# pi-shield.net
KiCad netlist of a schematic drawn in EAGLE
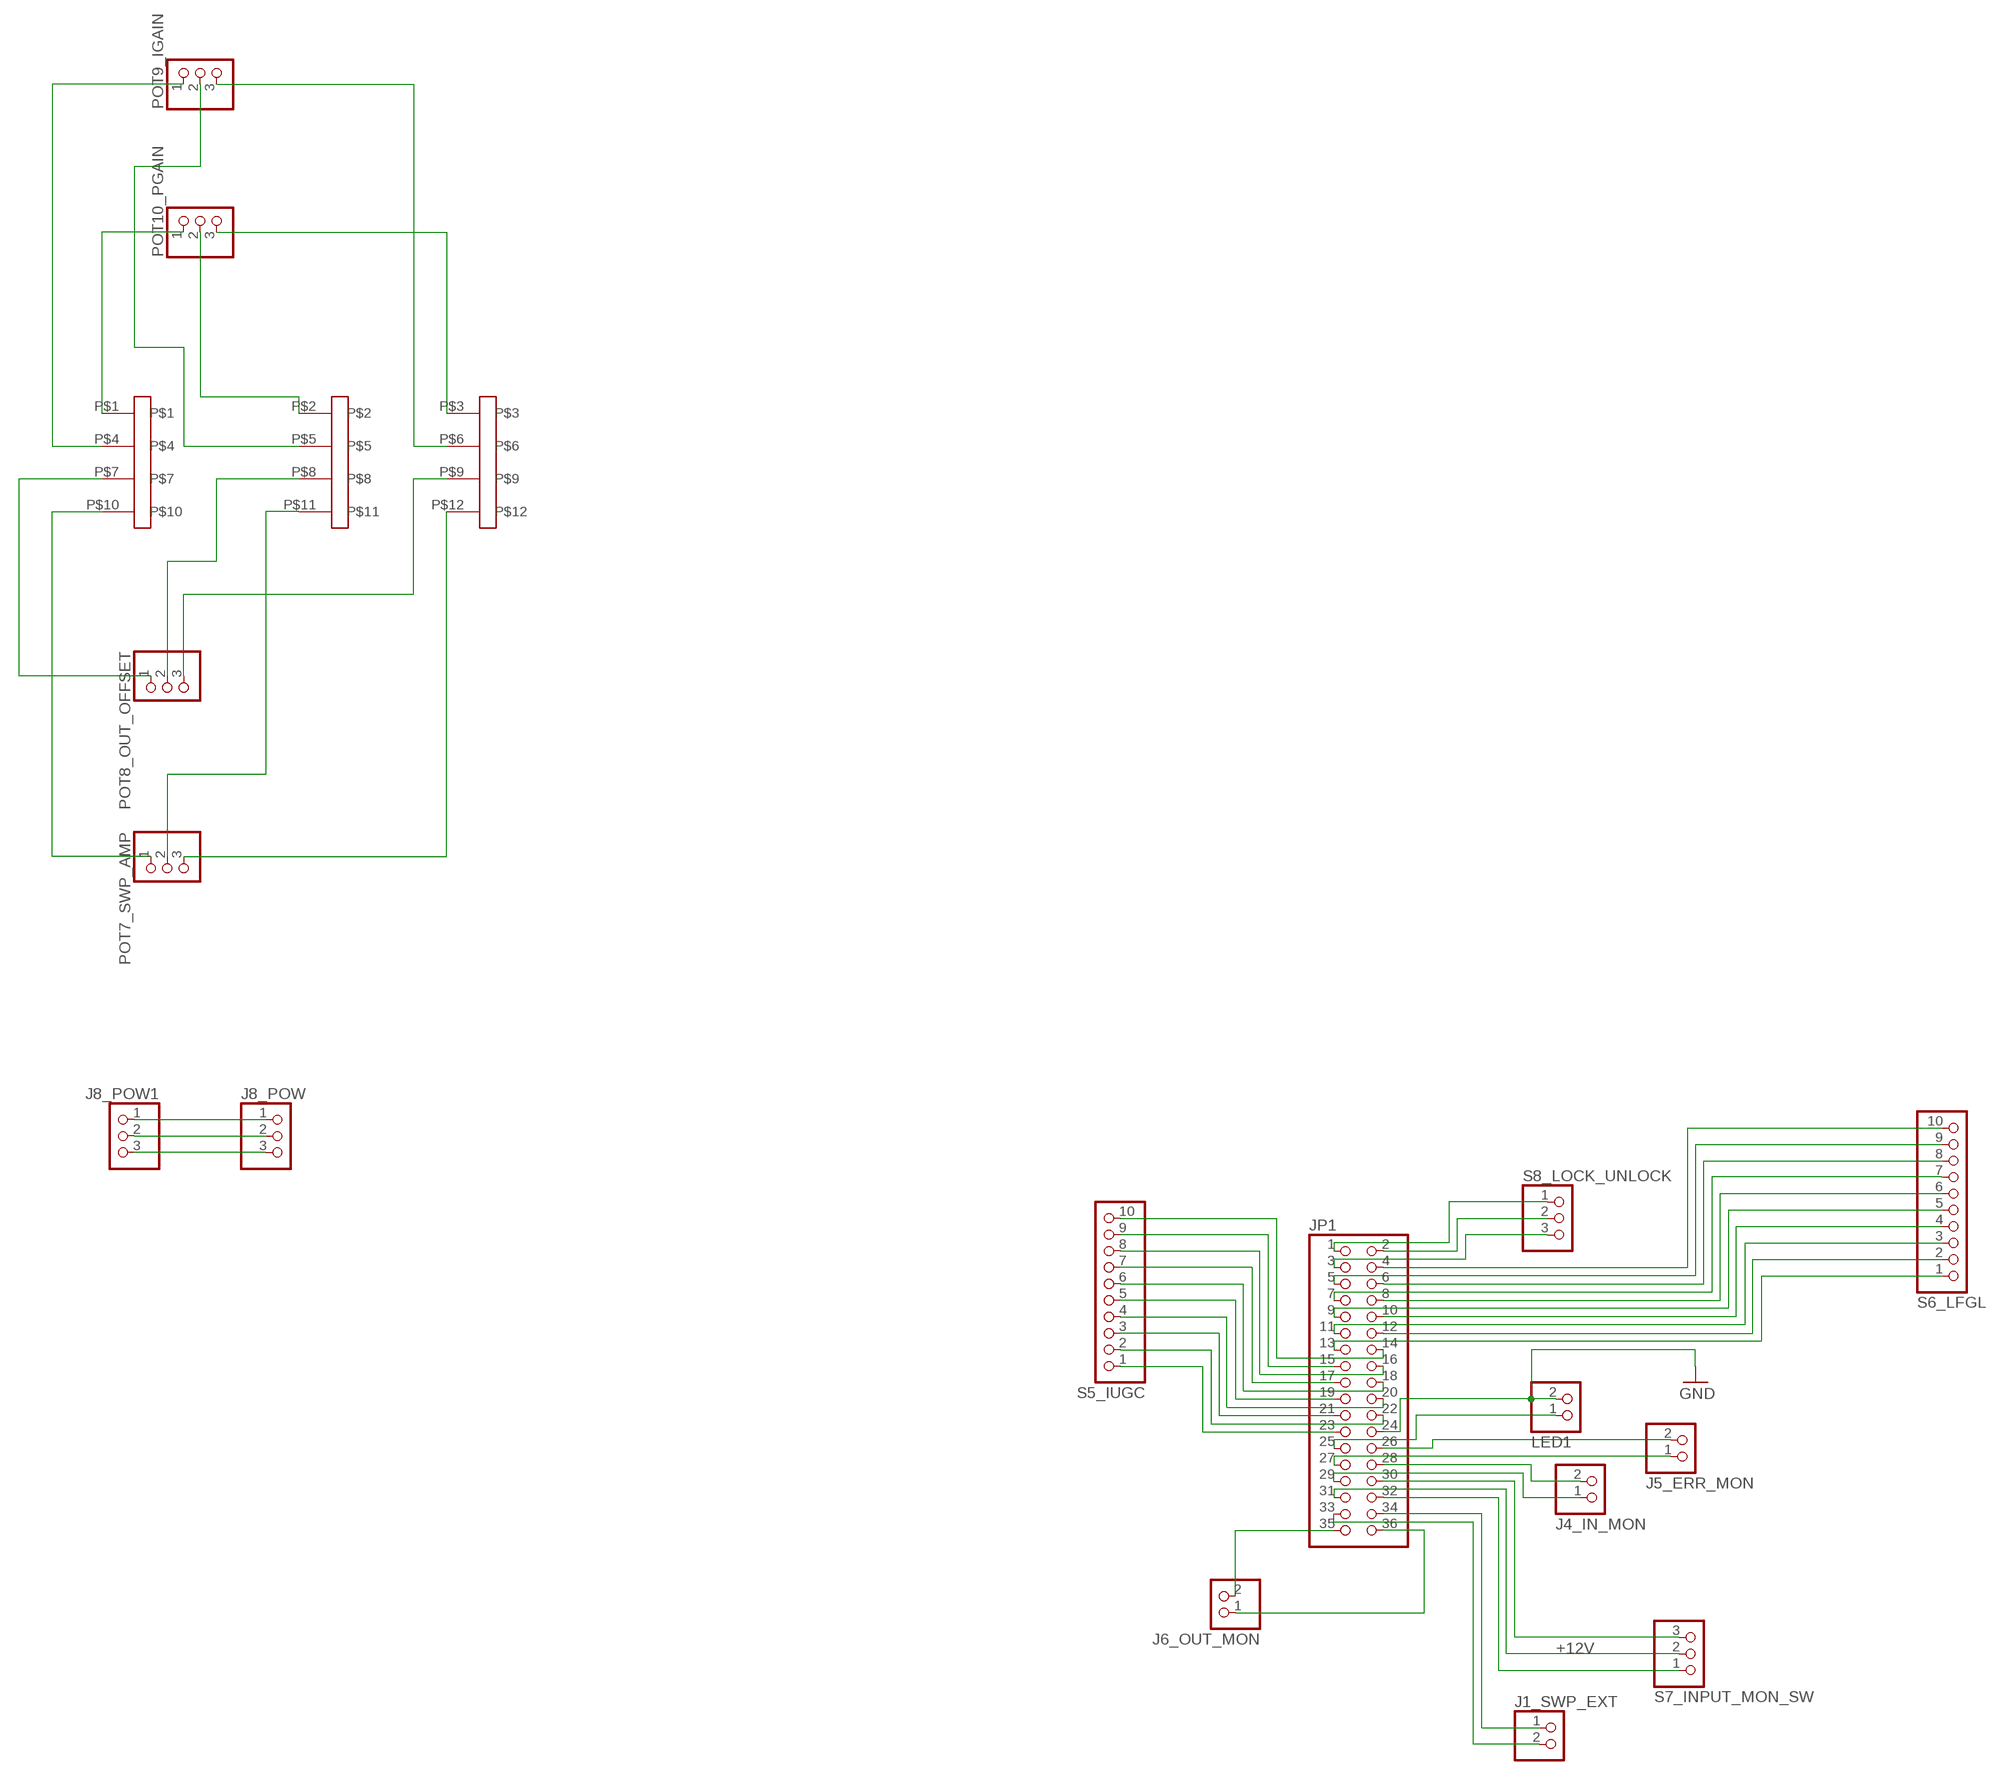
[diagram p0: schematic, sheet 1]

(export (version "E")
  (design (tool "Eeschema 10.0.6"))
  (components
    (comp (ref "J1")
      (value "PINHD-3X4")
      (footprint "eagle-import:3X04")
      (fields (field (name "PARTNO") "S7071-ND (2x)"))
      (libsource (lib "eagle-import") (part "PINHD-3X4"))
    )
    (comp (ref "J1_SWP_EXT")
      (value "PINHD-1X2")
      (footprint "eagle-import:1X02")
      (fields (field (name "PARTNO") "S7000-ND"))
      (libsource (lib "eagle-import") (part "PINHD-1X2"))
    )
    (comp (ref "J4_IN_MON")
      (value "PINHD-1X2")
      (footprint "eagle-import:1X02")
      (fields (field (name "PARTNO") "S7000-ND"))
      (libsource (lib "eagle-import") (part "PINHD-1X2"))
    )
    (comp (ref "J5_ERR_MON")
      (value "PINHD-1X2")
      (footprint "eagle-import:1X02")
      (fields (field (name "PARTNO") "S7000-ND"))
      (libsource (lib "eagle-import") (part "PINHD-1X2"))
    )
    (comp (ref "J6_OUT_MON")
      (value "PINHD-1X2")
      (footprint "eagle-import:1X02")
      (fields (field (name "PARTNO") "S7000-ND"))
      (libsource (lib "eagle-import") (part "PINHD-1X2"))
    )
    (comp (ref "J8_POW")
      (value "PINHD-1X3")
      (footprint "eagle-import:1X03")
      (fields (field (name "PARTNO") "S7036-ND"))
      (libsource (lib "eagle-import") (part "PINHD-1X3"))
    )
    (comp (ref "J8_POW1")
      (value "PINHD-1X3")
      (footprint "eagle-import:1X03")
      (fields (field (name "PARTNO") "A19470-ND"))
      (libsource (lib "eagle-import") (part "PINHD-1X3"))
    )
    (comp (ref "JP1")
      (value "PINHD-2X18/90")
      (footprint "eagle-import:2X18_90")
      (fields (field (name "PARTNO") "S2111EC-18-ND"))
      (libsource (lib "eagle-import") (part "PINHD-2X18/90"))
    )
    (comp (ref "LED1")
      (value "PINHD-1X2")
      (footprint "eagle-import:1X02")
      (fields (field (name "PARTNO") "S7000-ND"))
      (libsource (lib "eagle-import") (part "PINHD-1X2"))
    )
    (comp (ref "POT7_SWP_AMP")
      (value "PINHD-1X3")
      (footprint "eagle-import:1X03")
      (fields (field (name "PARTNO") "S7036-ND"))
      (libsource (lib "eagle-import") (part "PINHD-1X3"))
    )
    (comp (ref "POT8_OUT_OFFSET")
      (value "PINHD-1X3")
      (footprint "eagle-import:1X03")
      (fields (field (name "PARTNO") "S7036-ND"))
      (libsource (lib "eagle-import") (part "PINHD-1X3"))
    )
    (comp (ref "POT9_IGAIN")
      (value "PINHD-1X3")
      (footprint "eagle-import:1X03")
      (fields (field (name "PARTNO") "S7036-ND"))
      (libsource (lib "eagle-import") (part "PINHD-1X3"))
    )
    (comp (ref "POT10_PGAIN")
      (value "PINHD-1X3")
      (footprint "eagle-import:1X03")
      (fields (field (name "PARTNO") "S7036-ND"))
      (libsource (lib "eagle-import") (part "PINHD-1X3"))
    )
    (comp (ref "S5_IUGC")
      (value "PINHD-1X10")
      (footprint "eagle-import:1X10")
      (fields (field (name "PARTNO") "S7008-ND"))
      (libsource (lib "eagle-import") (part "PINHD-1X10"))
    )
    (comp (ref "S6_LFGL")
      (value "PINHD-1X10")
      (footprint "eagle-import:1X10")
      (fields (field (name "PARTNO") "S7008-ND"))
      (libsource (lib "eagle-import") (part "PINHD-1X10"))
    )
    (comp (ref "S7_INPUT_MON_SW")
      (value "PINHD-1X3")
      (footprint "eagle-import:1X03")
      (fields (field (name "PARTNO") "S7036-ND"))
      (libsource (lib "eagle-import") (part "PINHD-1X3"))
    )
    (comp (ref "S8_LOCK_UNLOCK")
      (value "PINHD-1X3")
      (footprint "eagle-import:1X03")
      (fields (field (name "PARTNO") "S7036-ND"))
      (libsource (lib "eagle-import") (part "PINHD-1X3"))
    )
  )
  (nets
    (net (code "1") (name "/+12V") (class "Default")
      (node (ref "JP1") (pin "31") (pinfunction "31_31") (pintype "passive"))
      (node (ref "S7_INPUT_MON_SW") (pin "2") (pinfunction "2_2") (pintype "passive"))
    )
    (net (code "2") (name "GND") (class "Default")
      (node (ref "JP1") (pin "24") (pinfunction "24_24") (pintype "passive"))
      (node (ref "LED1") (pin "2") (pinfunction "2_2") (pintype "passive"))
    )
    (net (code "3") (name "Net-(J1-PadP$1)") (class "Default")
      (node (ref "J1") (pin "P$1") (pinfunction "P$1_P$1") (pintype "bidirectional"))
      (node (ref "POT10_PGAIN") (pin "1") (pinfunction "1_1") (pintype "passive"))
    )
    (net (code "4") (name "Net-(J1-PadP$2)") (class "Default")
      (node (ref "J1") (pin "P$2") (pinfunction "P$2_P$2") (pintype "bidirectional"))
      (node (ref "POT10_PGAIN") (pin "2") (pinfunction "2_2") (pintype "passive"))
    )
    (net (code "5") (name "Net-(J1-PadP$3)") (class "Default")
      (node (ref "J1") (pin "P$3") (pinfunction "P$3_P$3") (pintype "bidirectional"))
      (node (ref "POT10_PGAIN") (pin "3") (pinfunction "3_3") (pintype "passive"))
    )
    (net (code "6") (name "Net-(J1-PadP$4)") (class "Default")
      (node (ref "J1") (pin "P$4") (pinfunction "P$4_P$4") (pintype "bidirectional"))
      (node (ref "POT9_IGAIN") (pin "1") (pinfunction "1_1") (pintype "passive"))
    )
    (net (code "7") (name "Net-(J1-PadP$5)") (class "Default")
      (node (ref "J1") (pin "P$5") (pinfunction "P$5_P$5") (pintype "bidirectional"))
      (node (ref "POT9_IGAIN") (pin "2") (pinfunction "2_2") (pintype "passive"))
    )
    (net (code "8") (name "Net-(J1-PadP$6)") (class "Default")
      (node (ref "J1") (pin "P$6") (pinfunction "P$6_P$6") (pintype "bidirectional"))
      (node (ref "POT9_IGAIN") (pin "3") (pinfunction "3_3") (pintype "passive"))
    )
    (net (code "9") (name "Net-(J1-PadP$7)") (class "Default")
      (node (ref "J1") (pin "P$7") (pinfunction "P$7_P$7") (pintype "bidirectional"))
      (node (ref "POT8_OUT_OFFSET") (pin "1") (pinfunction "1_1") (pintype "passive"))
    )
    (net (code "10") (name "Net-(J1-PadP$8)") (class "Default")
      (node (ref "J1") (pin "P$8") (pinfunction "P$8_P$8") (pintype "bidirectional"))
      (node (ref "POT8_OUT_OFFSET") (pin "2") (pinfunction "2_2") (pintype "passive"))
    )
    (net (code "11") (name "Net-(J1-PadP$9)") (class "Default")
      (node (ref "J1") (pin "P$9") (pinfunction "P$9_P$9") (pintype "bidirectional"))
      (node (ref "POT8_OUT_OFFSET") (pin "3") (pinfunction "3_3") (pintype "passive"))
    )
    (net (code "12") (name "Net-(J1-PadP$10)") (class "Default")
      (node (ref "J1") (pin "P$10") (pinfunction "P$10_P$10") (pintype "bidirectional"))
      (node (ref "POT7_SWP_AMP") (pin "1") (pinfunction "1_1") (pintype "passive"))
    )
    (net (code "13") (name "Net-(J1-PadP$11)") (class "Default")
      (node (ref "J1") (pin "P$11") (pinfunction "P$11_P$11") (pintype "bidirectional"))
      (node (ref "POT7_SWP_AMP") (pin "2") (pinfunction "2_2") (pintype "passive"))
    )
    (net (code "14") (name "Net-(J1-PadP$12)") (class "Default")
      (node (ref "J1") (pin "P$12") (pinfunction "P$12_P$12") (pintype "bidirectional"))
      (node (ref "POT7_SWP_AMP") (pin "3") (pinfunction "3_3") (pintype "passive"))
    )
    (net (code "15") (name "Net-(J1_SWP_EXT-Pad1)") (class "Default")
      (node (ref "J1_SWP_EXT") (pin "1") (pinfunction "1_1") (pintype "passive"))
      (node (ref "JP1") (pin "34") (pinfunction "34_34") (pintype "passive"))
    )
    (net (code "16") (name "Net-(J1_SWP_EXT-Pad2)") (class "Default")
      (node (ref "J1_SWP_EXT") (pin "2") (pinfunction "2_2") (pintype "passive"))
      (node (ref "JP1") (pin "33") (pinfunction "33_33") (pintype "passive"))
    )
    (net (code "17") (name "Net-(J4_IN_MON-Pad1)") (class "Default")
      (node (ref "J4_IN_MON") (pin "1") (pinfunction "1_1") (pintype "passive"))
      (node (ref "JP1") (pin "29") (pinfunction "29_29") (pintype "passive"))
    )
    (net (code "18") (name "Net-(J4_IN_MON-Pad2)") (class "Default")
      (node (ref "J4_IN_MON") (pin "2") (pinfunction "2_2") (pintype "passive"))
      (node (ref "JP1") (pin "28") (pinfunction "28_28") (pintype "passive"))
    )
    (net (code "19") (name "Net-(J5_ERR_MON-Pad1)") (class "Default")
      (node (ref "J5_ERR_MON") (pin "1") (pinfunction "1_1") (pintype "passive"))
      (node (ref "JP1") (pin "27") (pinfunction "27_27") (pintype "passive"))
    )
    (net (code "20") (name "Net-(J5_ERR_MON-Pad2)") (class "Default")
      (node (ref "J5_ERR_MON") (pin "2") (pinfunction "2_2") (pintype "passive"))
      (node (ref "JP1") (pin "26") (pinfunction "26_26") (pintype "passive"))
    )
    (net (code "21") (name "Net-(J6_OUT_MON-Pad1)") (class "Default")
      (node (ref "J6_OUT_MON") (pin "1") (pinfunction "1_1") (pintype "passive"))
      (node (ref "JP1") (pin "36") (pinfunction "36_36") (pintype "passive"))
    )
    (net (code "22") (name "Net-(J6_OUT_MON-Pad2)") (class "Default")
      (node (ref "J6_OUT_MON") (pin "2") (pinfunction "2_2") (pintype "passive"))
      (node (ref "JP1") (pin "35") (pinfunction "35_35") (pintype "passive"))
    )
    (net (code "23") (name "Net-(J8_POW-Pad1)") (class "Default")
      (node (ref "J8_POW") (pin "1") (pinfunction "1_1") (pintype "passive"))
      (node (ref "J8_POW1") (pin "1") (pinfunction "1_1") (pintype "passive"))
    )
    (net (code "24") (name "Net-(J8_POW-Pad2)") (class "Default")
      (node (ref "J8_POW") (pin "2") (pinfunction "2_2") (pintype "passive"))
      (node (ref "J8_POW1") (pin "2") (pinfunction "2_2") (pintype "passive"))
    )
    (net (code "25") (name "Net-(J8_POW-Pad3)") (class "Default")
      (node (ref "J8_POW") (pin "3") (pinfunction "3_3") (pintype "passive"))
      (node (ref "J8_POW1") (pin "3") (pinfunction "3_3") (pintype "passive"))
    )
    (net (code "26") (name "Net-(JP1-Pad1)") (class "Default")
      (node (ref "JP1") (pin "1") (pinfunction "1_1") (pintype "passive"))
      (node (ref "S8_LOCK_UNLOCK") (pin "1") (pinfunction "1_1") (pintype "passive"))
    )
    (net (code "27") (name "Net-(JP1-Pad2)") (class "Default")
      (node (ref "JP1") (pin "2") (pinfunction "2_2") (pintype "passive"))
      (node (ref "S8_LOCK_UNLOCK") (pin "2") (pinfunction "2_2") (pintype "passive"))
    )
    (net (code "28") (name "Net-(JP1-Pad3)") (class "Default")
      (node (ref "JP1") (pin "3") (pinfunction "3_3") (pintype "passive"))
      (node (ref "S8_LOCK_UNLOCK") (pin "3") (pinfunction "3_3") (pintype "passive"))
    )
    (net (code "29") (name "Net-(JP1-Pad4)") (class "Default")
      (node (ref "JP1") (pin "4") (pinfunction "4_4") (pintype "passive"))
      (node (ref "S6_LFGL") (pin "10") (pinfunction "10_10") (pintype "passive"))
    )
    (net (code "30") (name "Net-(JP1-Pad5)") (class "Default")
      (node (ref "JP1") (pin "5") (pinfunction "5_5") (pintype "passive"))
      (node (ref "S6_LFGL") (pin "9") (pinfunction "9_9") (pintype "passive"))
    )
    (net (code "31") (name "Net-(JP1-Pad6)") (class "Default")
      (node (ref "JP1") (pin "6") (pinfunction "6_6") (pintype "passive"))
      (node (ref "S6_LFGL") (pin "8") (pinfunction "8_8") (pintype "passive"))
    )
    (net (code "32") (name "Net-(JP1-Pad7)") (class "Default")
      (node (ref "JP1") (pin "7") (pinfunction "7_7") (pintype "passive"))
      (node (ref "S6_LFGL") (pin "7") (pinfunction "7_7") (pintype "passive"))
    )
    (net (code "33") (name "Net-(JP1-Pad8)") (class "Default")
      (node (ref "JP1") (pin "8") (pinfunction "8_8") (pintype "passive"))
      (node (ref "S6_LFGL") (pin "6") (pinfunction "6_6") (pintype "passive"))
    )
    (net (code "34") (name "Net-(JP1-Pad9)") (class "Default")
      (node (ref "JP1") (pin "9") (pinfunction "9_9") (pintype "passive"))
      (node (ref "S6_LFGL") (pin "5") (pinfunction "5_5") (pintype "passive"))
    )
    (net (code "35") (name "Net-(JP1-Pad10)") (class "Default")
      (node (ref "JP1") (pin "10") (pinfunction "10_10") (pintype "passive"))
      (node (ref "S6_LFGL") (pin "4") (pinfunction "4_4") (pintype "passive"))
    )
    (net (code "36") (name "Net-(JP1-Pad11)") (class "Default")
      (node (ref "JP1") (pin "11") (pinfunction "11_11") (pintype "passive"))
      (node (ref "S6_LFGL") (pin "3") (pinfunction "3_3") (pintype "passive"))
    )
    (net (code "37") (name "Net-(JP1-Pad12)") (class "Default")
      (node (ref "JP1") (pin "12") (pinfunction "12_12") (pintype "passive"))
      (node (ref "S6_LFGL") (pin "2") (pinfunction "2_2") (pintype "passive"))
    )
    (net (code "38") (name "Net-(JP1-Pad13)") (class "Default")
      (node (ref "JP1") (pin "13") (pinfunction "13_13") (pintype "passive"))
      (node (ref "S6_LFGL") (pin "1") (pinfunction "1_1") (pintype "passive"))
    )
    (net (code "39") (name "Net-(JP1-Pad14)") (class "Default")
      (node (ref "JP1") (pin "14") (pinfunction "14_14") (pintype "passive"))
      (node (ref "S5_IUGC") (pin "10") (pinfunction "10_10") (pintype "passive"))
    )
    (net (code "40") (name "Net-(JP1-Pad15)") (class "Default")
      (node (ref "JP1") (pin "15") (pinfunction "15_15") (pintype "passive"))
      (node (ref "S5_IUGC") (pin "9") (pinfunction "9_9") (pintype "passive"))
    )
    (net (code "41") (name "Net-(JP1-Pad16)") (class "Default")
      (node (ref "JP1") (pin "16") (pinfunction "16_16") (pintype "passive"))
      (node (ref "S5_IUGC") (pin "8") (pinfunction "8_8") (pintype "passive"))
    )
    (net (code "42") (name "Net-(JP1-Pad17)") (class "Default")
      (node (ref "JP1") (pin "17") (pinfunction "17_17") (pintype "passive"))
      (node (ref "S5_IUGC") (pin "7") (pinfunction "7_7") (pintype "passive"))
    )
    (net (code "43") (name "Net-(JP1-Pad18)") (class "Default")
      (node (ref "JP1") (pin "18") (pinfunction "18_18") (pintype "passive"))
      (node (ref "S5_IUGC") (pin "6") (pinfunction "6_6") (pintype "passive"))
    )
    (net (code "44") (name "Net-(JP1-Pad19)") (class "Default")
      (node (ref "JP1") (pin "19") (pinfunction "19_19") (pintype "passive"))
      (node (ref "S5_IUGC") (pin "5") (pinfunction "5_5") (pintype "passive"))
    )
    (net (code "45") (name "Net-(JP1-Pad20)") (class "Default")
      (node (ref "JP1") (pin "20") (pinfunction "20_20") (pintype "passive"))
      (node (ref "S5_IUGC") (pin "4") (pinfunction "4_4") (pintype "passive"))
    )
    (net (code "46") (name "Net-(JP1-Pad21)") (class "Default")
      (node (ref "JP1") (pin "21") (pinfunction "21_21") (pintype "passive"))
      (node (ref "S5_IUGC") (pin "3") (pinfunction "3_3") (pintype "passive"))
    )
    (net (code "47") (name "Net-(JP1-Pad22)") (class "Default")
      (node (ref "JP1") (pin "22") (pinfunction "22_22") (pintype "passive"))
      (node (ref "S5_IUGC") (pin "2") (pinfunction "2_2") (pintype "passive"))
    )
    (net (code "48") (name "Net-(JP1-Pad23)") (class "Default")
      (node (ref "JP1") (pin "23") (pinfunction "23_23") (pintype "passive"))
      (node (ref "S5_IUGC") (pin "1") (pinfunction "1_1") (pintype "passive"))
    )
    (net (code "49") (name "Net-(JP1-Pad25)") (class "Default")
      (node (ref "JP1") (pin "25") (pinfunction "25_25") (pintype "passive"))
      (node (ref "LED1") (pin "1") (pinfunction "1_1") (pintype "passive"))
    )
    (net (code "50") (name "Net-(JP1-Pad30)") (class "Default")
      (node (ref "JP1") (pin "30") (pinfunction "30_30") (pintype "passive"))
      (node (ref "S7_INPUT_MON_SW") (pin "3") (pinfunction "3_3") (pintype "passive"))
    )
    (net (code "51") (name "Net-(JP1-Pad32)") (class "Default")
      (node (ref "JP1") (pin "32") (pinfunction "32_32") (pintype "passive"))
      (node (ref "S7_INPUT_MON_SW") (pin "1") (pinfunction "1_1") (pintype "passive"))
    )
  )
)
